# LiTE_INO_2_2_rev_01_GND_Plan.net
KiCad netlist of a schematic drawn in EAGLE
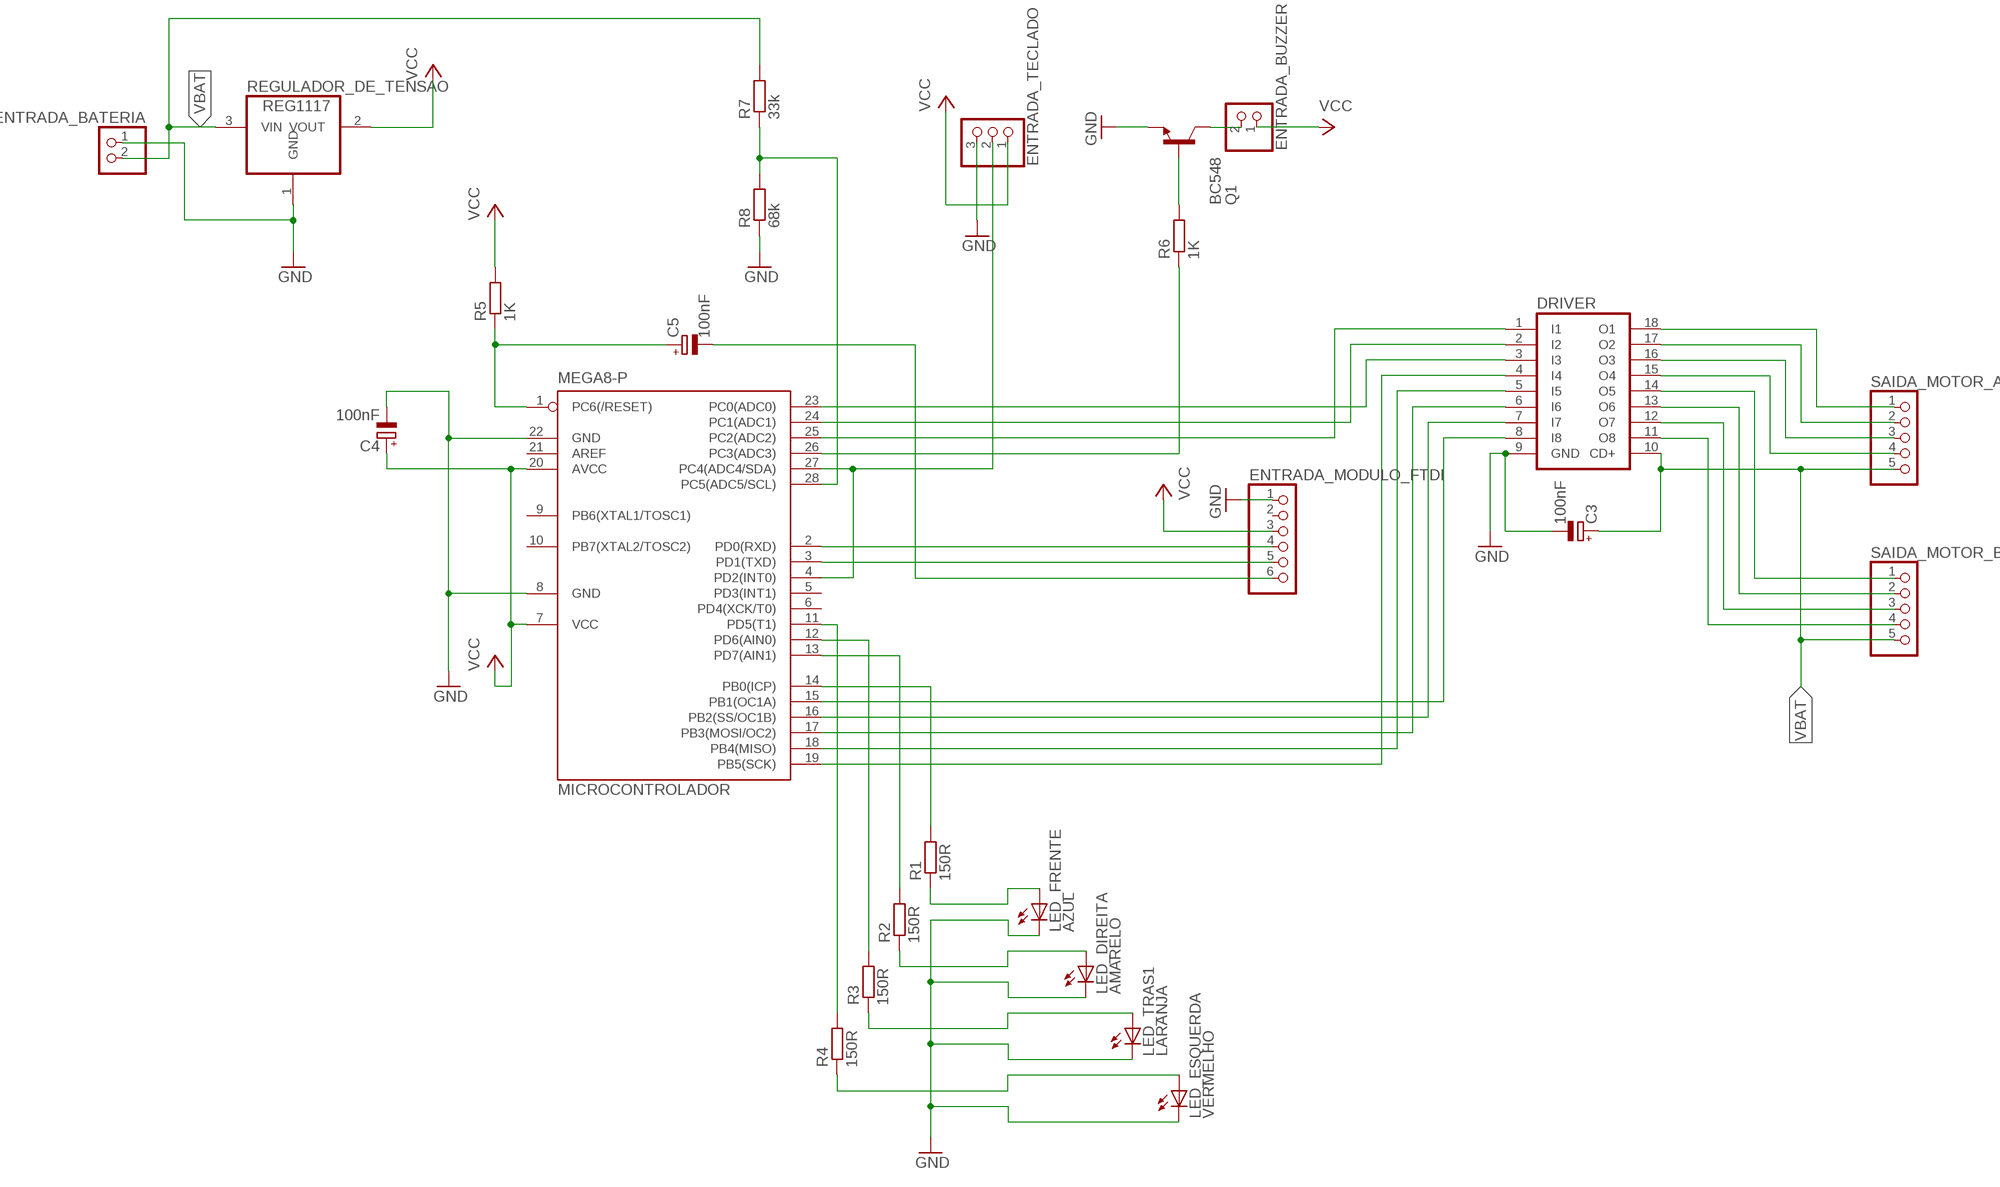
[diagram p0: schematic, sheet 1]

(export (version "E")
  (design (tool "Eeschema 10.0.6"))
  (components
    (comp (ref "C3")
      (value "100nF")
      (footprint "eagle-import:E5-5")
      (libsource (lib "eagle-import") (part "CPOL-EUE5-5"))
    )
    (comp (ref "C4")
      (value "100nF")
      (footprint "eagle-import:E5-5")
      (libsource (lib "eagle-import") (part "CPOL-EUE5-5"))
    )
    (comp (ref "C5")
      (value "100nF")
      (footprint "eagle-import:E5-5")
      (libsource (lib "eagle-import") (part "CPOL-EUE5-5"))
    )
    (comp (ref "DRIVER")
      (value "ULN2803A")
      (footprint "eagle-import:DIL18")
      (libsource (lib "eagle-import") (part "ULN2803A"))
    )
    (comp (ref "ENTRADA_BATERIA")
      (value "PINHD-1X2/90")
      (footprint "eagle-import:1X02_90")
      (libsource (lib "eagle-import") (part "PINHD-1X2/90"))
    )
    (comp (ref "ENTRADA_BUZZER")
      (value "PINHD-1X2/90")
      (footprint "eagle-import:1X02_90")
      (libsource (lib "eagle-import") (part "PINHD-1X2/90"))
    )
    (comp (ref "ENTRADA_MODULO_FTDI")
      (value "PINHD-1X6/90")
      (footprint "eagle-import:1X06_90")
      (libsource (lib "eagle-import") (part "PINHD-1X6/90"))
    )
    (comp (ref "ENTRADA_TECLADO")
      (value "PINHD-1X3/90")
      (footprint "eagle-import:1X03_90")
      (libsource (lib "eagle-import") (part "PINHD-1X3/90"))
    )
    (comp (ref "LED_DIREITA")
      (value "AMARELO")
      (footprint "eagle-import:LED5MM")
      (libsource (lib "eagle-import") (part "LED5MM"))
    )
    (comp (ref "LED_ESQUERDA")
      (value "VERMELHO")
      (footprint "eagle-import:LED5MM")
      (libsource (lib "eagle-import") (part "LED5MM"))
    )
    (comp (ref "LED_FRENTE")
      (value "AZUL")
      (footprint "eagle-import:LED5MM")
      (libsource (lib "eagle-import") (part "LED5MM"))
    )
    (comp (ref "LED_TRAS1")
      (value "LARANJA")
      (footprint "eagle-import:LED5MM")
      (libsource (lib "eagle-import") (part "LED5MM"))
    )
    (comp (ref "MICROCONTROLADOR")
      (value "MEGA8-P")
      (footprint "eagle-import:DIL28-3")
      (libsource (lib "eagle-import") (part "MEGA8-P"))
    )
    (comp (ref "Q1")
      (value "BC548")
      (footprint "eagle-import:TO92-EBC")
      (libsource (lib "eagle-import") (part "BC548"))
    )
    (comp (ref "R1")
      (value "150R")
      (footprint "eagle-import:0204_7")
      (libsource (lib "eagle-import") (part "R-EU_0204/7"))
    )
    (comp (ref "R2")
      (value "150R")
      (footprint "eagle-import:0204_7")
      (libsource (lib "eagle-import") (part "R-EU_0204/7"))
    )
    (comp (ref "R3")
      (value "150R")
      (footprint "eagle-import:0204_7")
      (libsource (lib "eagle-import") (part "R-EU_0204/7"))
    )
    (comp (ref "R4")
      (value "150R")
      (footprint "eagle-import:0204_7")
      (libsource (lib "eagle-import") (part "R-EU_0204/7"))
    )
    (comp (ref "R5")
      (value "1K")
      (footprint "eagle-import:0204_7")
      (libsource (lib "eagle-import") (part "R-EU_0204/7"))
    )
    (comp (ref "R6")
      (value "1K")
      (footprint "eagle-import:0204_7")
      (libsource (lib "eagle-import") (part "R-EU_0204/7"))
    )
    (comp (ref "R7")
      (value "33k")
      (footprint "eagle-import:0204_7")
      (libsource (lib "eagle-import") (part "R-EU_0204/7"))
    )
    (comp (ref "R8")
      (value "68k")
      (footprint "eagle-import:0204_7")
      (libsource (lib "eagle-import") (part "R-EU_0204/7"))
    )
    (comp (ref "REGULADOR_DE_TENSAO")
      (value "REG1117")
      (footprint "eagle-import:SOT223")
      (libsource (lib "eagle-import") (part "REG1117"))
    )
    (comp (ref "SAIDA_MOTOR_A")
      (value "PINHD-1X5/90")
      (footprint "eagle-import:1X05_90")
      (libsource (lib "eagle-import") (part "PINHD-1X5/90"))
    )
    (comp (ref "SAIDA_MOTOR_B")
      (value "PINHD-1X5/90")
      (footprint "eagle-import:1X05_90")
      (libsource (lib "eagle-import") (part "PINHD-1X5/90"))
    )
  )
  (nets
    (net (code "1") (name "GND") (class "Default")
      (node (ref "C3") (pin "-") (pinfunction "-_-") (pintype "passive"))
      (node (ref "C4") (pin "-") (pinfunction "-_-") (pintype "passive"))
      (node (ref "DRIVER") (pin "9") (pinfunction "GND_9") (pintype "power_in"))
      (node (ref "ENTRADA_BATERIA") (pin "1") (pinfunction "1_1") (pintype "passive"))
      (node (ref "ENTRADA_MODULO_FTDI") (pin "1") (pinfunction "1_1") (pintype "passive"))
      (node (ref "ENTRADA_TECLADO") (pin "3") (pinfunction "3_3") (pintype "passive"))
      (node (ref "LED_DIREITA") (pin "K") (pinfunction "C_K") (pintype "passive"))
      (node (ref "LED_ESQUERDA") (pin "K") (pinfunction "C_K") (pintype "passive"))
      (node (ref "LED_FRENTE") (pin "K") (pinfunction "C_K") (pintype "passive"))
      (node (ref "LED_TRAS1") (pin "K") (pinfunction "C_K") (pintype "passive"))
      (node (ref "MICROCONTROLADOR") (pin "22") (pinfunction "GND_22") (pintype "power_in"))
      (node (ref "MICROCONTROLADOR") (pin "8") (pinfunction "GND_8") (pintype "power_in"))
      (node (ref "Q1") (pin "E") (pinfunction "E_E") (pintype "passive"))
      (node (ref "R8") (pin "1") (pinfunction "1_1") (pintype "passive"))
      (node (ref "REGULADOR_DE_TENSAO") (pin "1") (pinfunction "GND_1") (pintype "power_in"))
    )
    (net (code "2") (name "Net-(C5-Pad-)") (class "Default")
      (node (ref "C5") (pin "-") (pinfunction "-_-") (pintype "passive"))
      (node (ref "ENTRADA_MODULO_FTDI") (pin "6") (pinfunction "6_6") (pintype "passive"))
    )
    (net (code "3") (name "Net-(DRIVER-I1)") (class "Default")
      (node (ref "DRIVER") (pin "1") (pinfunction "I1_1") (pintype "input"))
      (node (ref "MICROCONTROLADOR") (pin "25") (pinfunction "PC2(ADC2)_25") (pintype "bidirectional"))
    )
    (net (code "4") (name "Net-(DRIVER-I2)") (class "Default")
      (node (ref "DRIVER") (pin "2") (pinfunction "I2_2") (pintype "input"))
      (node (ref "MICROCONTROLADOR") (pin "24") (pinfunction "PC1(ADC1)_24") (pintype "bidirectional"))
    )
    (net (code "5") (name "Net-(DRIVER-I3)") (class "Default")
      (node (ref "DRIVER") (pin "3") (pinfunction "I3_3") (pintype "input"))
      (node (ref "MICROCONTROLADOR") (pin "23") (pinfunction "PC0(ADC0)_23") (pintype "bidirectional"))
    )
    (net (code "6") (name "Net-(DRIVER-I4)") (class "Default")
      (node (ref "DRIVER") (pin "4") (pinfunction "I4_4") (pintype "input"))
      (node (ref "MICROCONTROLADOR") (pin "19") (pinfunction "PB5(SCK)_19") (pintype "bidirectional"))
    )
    (net (code "7") (name "Net-(DRIVER-I5)") (class "Default")
      (node (ref "DRIVER") (pin "5") (pinfunction "I5_5") (pintype "input"))
      (node (ref "MICROCONTROLADOR") (pin "18") (pinfunction "PB4(MISO)_18") (pintype "bidirectional"))
    )
    (net (code "8") (name "Net-(DRIVER-I6)") (class "Default")
      (node (ref "DRIVER") (pin "6") (pinfunction "I6_6") (pintype "input"))
      (node (ref "MICROCONTROLADOR") (pin "17") (pinfunction "PB3(MOSI/OC2)_17") (pintype "bidirectional"))
    )
    (net (code "9") (name "Net-(DRIVER-I7)") (class "Default")
      (node (ref "DRIVER") (pin "7") (pinfunction "I7_7") (pintype "input"))
      (node (ref "MICROCONTROLADOR") (pin "16") (pinfunction "PB2(SS/OC1B)_16") (pintype "bidirectional"))
    )
    (net (code "10") (name "Net-(DRIVER-I8)") (class "Default")
      (node (ref "DRIVER") (pin "8") (pinfunction "I8_8") (pintype "input"))
      (node (ref "MICROCONTROLADOR") (pin "15") (pinfunction "PB1(OC1A)_15") (pintype "bidirectional"))
    )
    (net (code "11") (name "Net-(DRIVER-O1)") (class "Default")
      (node (ref "DRIVER") (pin "18") (pinfunction "O1_18") (pintype "open_collector"))
      (node (ref "SAIDA_MOTOR_A") (pin "1") (pinfunction "1_1") (pintype "passive"))
    )
    (net (code "12") (name "Net-(DRIVER-O2)") (class "Default")
      (node (ref "DRIVER") (pin "17") (pinfunction "O2_17") (pintype "open_collector"))
      (node (ref "SAIDA_MOTOR_A") (pin "2") (pinfunction "2_2") (pintype "passive"))
    )
    (net (code "13") (name "Net-(DRIVER-O3)") (class "Default")
      (node (ref "DRIVER") (pin "16") (pinfunction "O3_16") (pintype "open_collector"))
      (node (ref "SAIDA_MOTOR_A") (pin "3") (pinfunction "3_3") (pintype "passive"))
    )
    (net (code "14") (name "Net-(DRIVER-O4)") (class "Default")
      (node (ref "DRIVER") (pin "15") (pinfunction "O4_15") (pintype "open_collector"))
      (node (ref "SAIDA_MOTOR_A") (pin "4") (pinfunction "4_4") (pintype "passive"))
    )
    (net (code "15") (name "Net-(DRIVER-O5)") (class "Default")
      (node (ref "DRIVER") (pin "14") (pinfunction "O5_14") (pintype "open_collector"))
      (node (ref "SAIDA_MOTOR_B") (pin "1") (pinfunction "1_1") (pintype "passive"))
    )
    (net (code "16") (name "Net-(DRIVER-O6)") (class "Default")
      (node (ref "DRIVER") (pin "13") (pinfunction "O6_13") (pintype "open_collector"))
      (node (ref "SAIDA_MOTOR_B") (pin "2") (pinfunction "2_2") (pintype "passive"))
    )
    (net (code "17") (name "Net-(DRIVER-O7)") (class "Default")
      (node (ref "DRIVER") (pin "12") (pinfunction "O7_12") (pintype "open_collector"))
      (node (ref "SAIDA_MOTOR_B") (pin "3") (pinfunction "3_3") (pintype "passive"))
    )
    (net (code "18") (name "Net-(DRIVER-O8)") (class "Default")
      (node (ref "DRIVER") (pin "11") (pinfunction "O8_11") (pintype "open_collector"))
      (node (ref "SAIDA_MOTOR_B") (pin "4") (pinfunction "4_4") (pintype "passive"))
    )
    (net (code "19") (name "Net-(ENTRADA_BUZZER-Pad2)") (class "Default")
      (node (ref "ENTRADA_BUZZER") (pin "2") (pinfunction "2_2") (pintype "passive"))
      (node (ref "Q1") (pin "C") (pinfunction "C_C") (pintype "passive"))
    )
    (net (code "20") (name "Net-(LED_DIREITA-PadA)") (class "Default")
      (node (ref "LED_DIREITA") (pin "A") (pinfunction "A_A") (pintype "passive"))
      (node (ref "R2") (pin "1") (pinfunction "1_1") (pintype "passive"))
    )
    (net (code "21") (name "Net-(LED_ESQUERDA-PadA)") (class "Default")
      (node (ref "LED_ESQUERDA") (pin "A") (pinfunction "A_A") (pintype "passive"))
      (node (ref "R4") (pin "1") (pinfunction "1_1") (pintype "passive"))
    )
    (net (code "22") (name "Net-(LED_FRENTE-PadA)") (class "Default")
      (node (ref "LED_FRENTE") (pin "A") (pinfunction "A_A") (pintype "passive"))
      (node (ref "R1") (pin "1") (pinfunction "1_1") (pintype "passive"))
    )
    (net (code "23") (name "Net-(LED_TRAS1-PadA)") (class "Default")
      (node (ref "LED_TRAS1") (pin "A") (pinfunction "A_A") (pintype "passive"))
      (node (ref "R3") (pin "1") (pinfunction "1_1") (pintype "passive"))
    )
    (net (code "24") (name "Net-(MICROCONTROLADOR-PB0(ICP))") (class "Default")
      (node (ref "MICROCONTROLADOR") (pin "14") (pinfunction "PB0(ICP)_14") (pintype "bidirectional"))
      (node (ref "R1") (pin "2") (pinfunction "2_2") (pintype "passive"))
    )
    (net (code "25") (name "Net-(MICROCONTROLADOR-PC3(ADC3))") (class "Default")
      (node (ref "MICROCONTROLADOR") (pin "26") (pinfunction "PC3(ADC3)_26") (pintype "bidirectional"))
      (node (ref "R6") (pin "1") (pinfunction "1_1") (pintype "passive"))
    )
    (net (code "26") (name "Net-(MICROCONTROLADOR-PC4(ADC4{slash}SDA))") (class "Default")
      (node (ref "ENTRADA_TECLADO") (pin "2") (pinfunction "2_2") (pintype "passive"))
      (node (ref "MICROCONTROLADOR") (pin "27") (pinfunction "PC4(ADC4/SDA)_27") (pintype "bidirectional"))
      (node (ref "MICROCONTROLADOR") (pin "4") (pinfunction "PD2(INT0)_4") (pintype "bidirectional"))
    )
    (net (code "27") (name "Net-(MICROCONTROLADOR-PC5(ADC5{slash}SCL))") (class "Default")
      (node (ref "MICROCONTROLADOR") (pin "28") (pinfunction "PC5(ADC5/SCL)_28") (pintype "bidirectional"))
      (node (ref "R7") (pin "1") (pinfunction "1_1") (pintype "passive"))
      (node (ref "R8") (pin "2") (pinfunction "2_2") (pintype "passive"))
    )
    (net (code "28") (name "Net-(MICROCONTROLADOR-PC6({slash}RESET))") (class "Default")
      (node (ref "C5") (pin "+") (pinfunction "+_+") (pintype "passive"))
      (node (ref "MICROCONTROLADOR") (pin "1") (pinfunction "PC6(/RESET)_1") (pintype "bidirectional"))
      (node (ref "R5") (pin "1") (pinfunction "1_1") (pintype "passive"))
    )
    (net (code "29") (name "Net-(MICROCONTROLADOR-PD0(RXD))") (class "Default")
      (node (ref "ENTRADA_MODULO_FTDI") (pin "4") (pinfunction "4_4") (pintype "passive"))
      (node (ref "MICROCONTROLADOR") (pin "2") (pinfunction "PD0(RXD)_2") (pintype "bidirectional"))
    )
    (net (code "30") (name "Net-(MICROCONTROLADOR-PD1(TXD))") (class "Default")
      (node (ref "ENTRADA_MODULO_FTDI") (pin "5") (pinfunction "5_5") (pintype "passive"))
      (node (ref "MICROCONTROLADOR") (pin "3") (pinfunction "PD1(TXD)_3") (pintype "bidirectional"))
    )
    (net (code "31") (name "Net-(MICROCONTROLADOR-PD5(T1))") (class "Default")
      (node (ref "MICROCONTROLADOR") (pin "11") (pinfunction "PD5(T1)_11") (pintype "bidirectional"))
      (node (ref "R4") (pin "2") (pinfunction "2_2") (pintype "passive"))
    )
    (net (code "32") (name "Net-(MICROCONTROLADOR-PD6(AIN0))") (class "Default")
      (node (ref "MICROCONTROLADOR") (pin "12") (pinfunction "PD6(AIN0)_12") (pintype "bidirectional"))
      (node (ref "R3") (pin "2") (pinfunction "2_2") (pintype "passive"))
    )
    (net (code "33") (name "Net-(MICROCONTROLADOR-PD7(AIN1))") (class "Default")
      (node (ref "MICROCONTROLADOR") (pin "13") (pinfunction "PD7(AIN1)_13") (pintype "bidirectional"))
      (node (ref "R2") (pin "2") (pinfunction "2_2") (pintype "passive"))
    )
    (net (code "34") (name "Net-(Q1-PadB)") (class "Default")
      (node (ref "Q1") (pin "B") (pinfunction "B_B") (pintype "passive"))
      (node (ref "R6") (pin "2") (pinfunction "2_2") (pintype "passive"))
    )
    (net (code "35") (name "VBAT") (class "Default")
      (node (ref "C3") (pin "+") (pinfunction "+_+") (pintype "passive"))
      (node (ref "DRIVER") (pin "10") (pinfunction "CD+_10") (pintype "passive"))
      (node (ref "ENTRADA_BATERIA") (pin "2") (pinfunction "2_2") (pintype "passive"))
      (node (ref "R7") (pin "2") (pinfunction "2_2") (pintype "passive"))
      (node (ref "REGULADOR_DE_TENSAO") (pin "3") (pinfunction "VIN_3") (pintype "input"))
      (node (ref "SAIDA_MOTOR_A") (pin "5") (pinfunction "5_5") (pintype "passive"))
      (node (ref "SAIDA_MOTOR_B") (pin "5") (pinfunction "5_5") (pintype "passive"))
    )
    (net (code "36") (name "VCC") (class "Default")
      (node (ref "C4") (pin "+") (pinfunction "+_+") (pintype "passive"))
      (node (ref "ENTRADA_BUZZER") (pin "1") (pinfunction "1_1") (pintype "passive"))
      (node (ref "ENTRADA_MODULO_FTDI") (pin "3") (pinfunction "3_3") (pintype "passive"))
      (node (ref "ENTRADA_TECLADO") (pin "1") (pinfunction "1_1") (pintype "passive"))
      (node (ref "MICROCONTROLADOR") (pin "20") (pinfunction "AVCC_20") (pintype "power_in"))
      (node (ref "MICROCONTROLADOR") (pin "7") (pinfunction "VCC_7") (pintype "power_in"))
      (node (ref "R5") (pin "2") (pinfunction "2_2") (pintype "passive"))
      (node (ref "REGULADOR_DE_TENSAO") (pin "2") (pinfunction "VOUT_2") (pintype "output"))
    )
    (net (code "37") (name "unconnected-(ENTRADA_MODULO_FTDI-Pad2)") (class "Default")
      (node (ref "ENTRADA_MODULO_FTDI") (pin "2") (pinfunction "2_2") (pintype "passive"))
    )
    (net (code "38") (name "unconnected-(MICROCONTROLADOR-AREF-Pad21)") (class "Default")
      (node (ref "MICROCONTROLADOR") (pin "21") (pinfunction "AREF_21") (pintype "passive"))
    )
    (net (code "39") (name "unconnected-(MICROCONTROLADOR-PB6(XTAL1{slash}TOSC1)-Pad9)") (class "Default")
      (node (ref "MICROCONTROLADOR") (pin "9") (pinfunction "PB6(XTAL1/TOSC1)_9") (pintype "bidirectional"))
    )
    (net (code "40") (name "unconnected-(MICROCONTROLADOR-PB7(XTAL2{slash}TOSC2)-Pad10)") (class "Default")
      (node (ref "MICROCONTROLADOR") (pin "10") (pinfunction "PB7(XTAL2/TOSC2)_10") (pintype "bidirectional"))
    )
    (net (code "41") (name "unconnected-(MICROCONTROLADOR-PD3(INT1)-Pad5)") (class "Default")
      (node (ref "MICROCONTROLADOR") (pin "5") (pinfunction "PD3(INT1)_5") (pintype "bidirectional"))
    )
    (net (code "42") (name "unconnected-(MICROCONTROLADOR-PD4(XCK{slash}T0)-Pad6)") (class "Default")
      (node (ref "MICROCONTROLADOR") (pin "6") (pinfunction "PD4(XCK/T0)_6") (pintype "bidirectional"))
    )
  )
)
